# MidiMon_v3.net
KiCad netlist of a schematic drawn in EAGLE
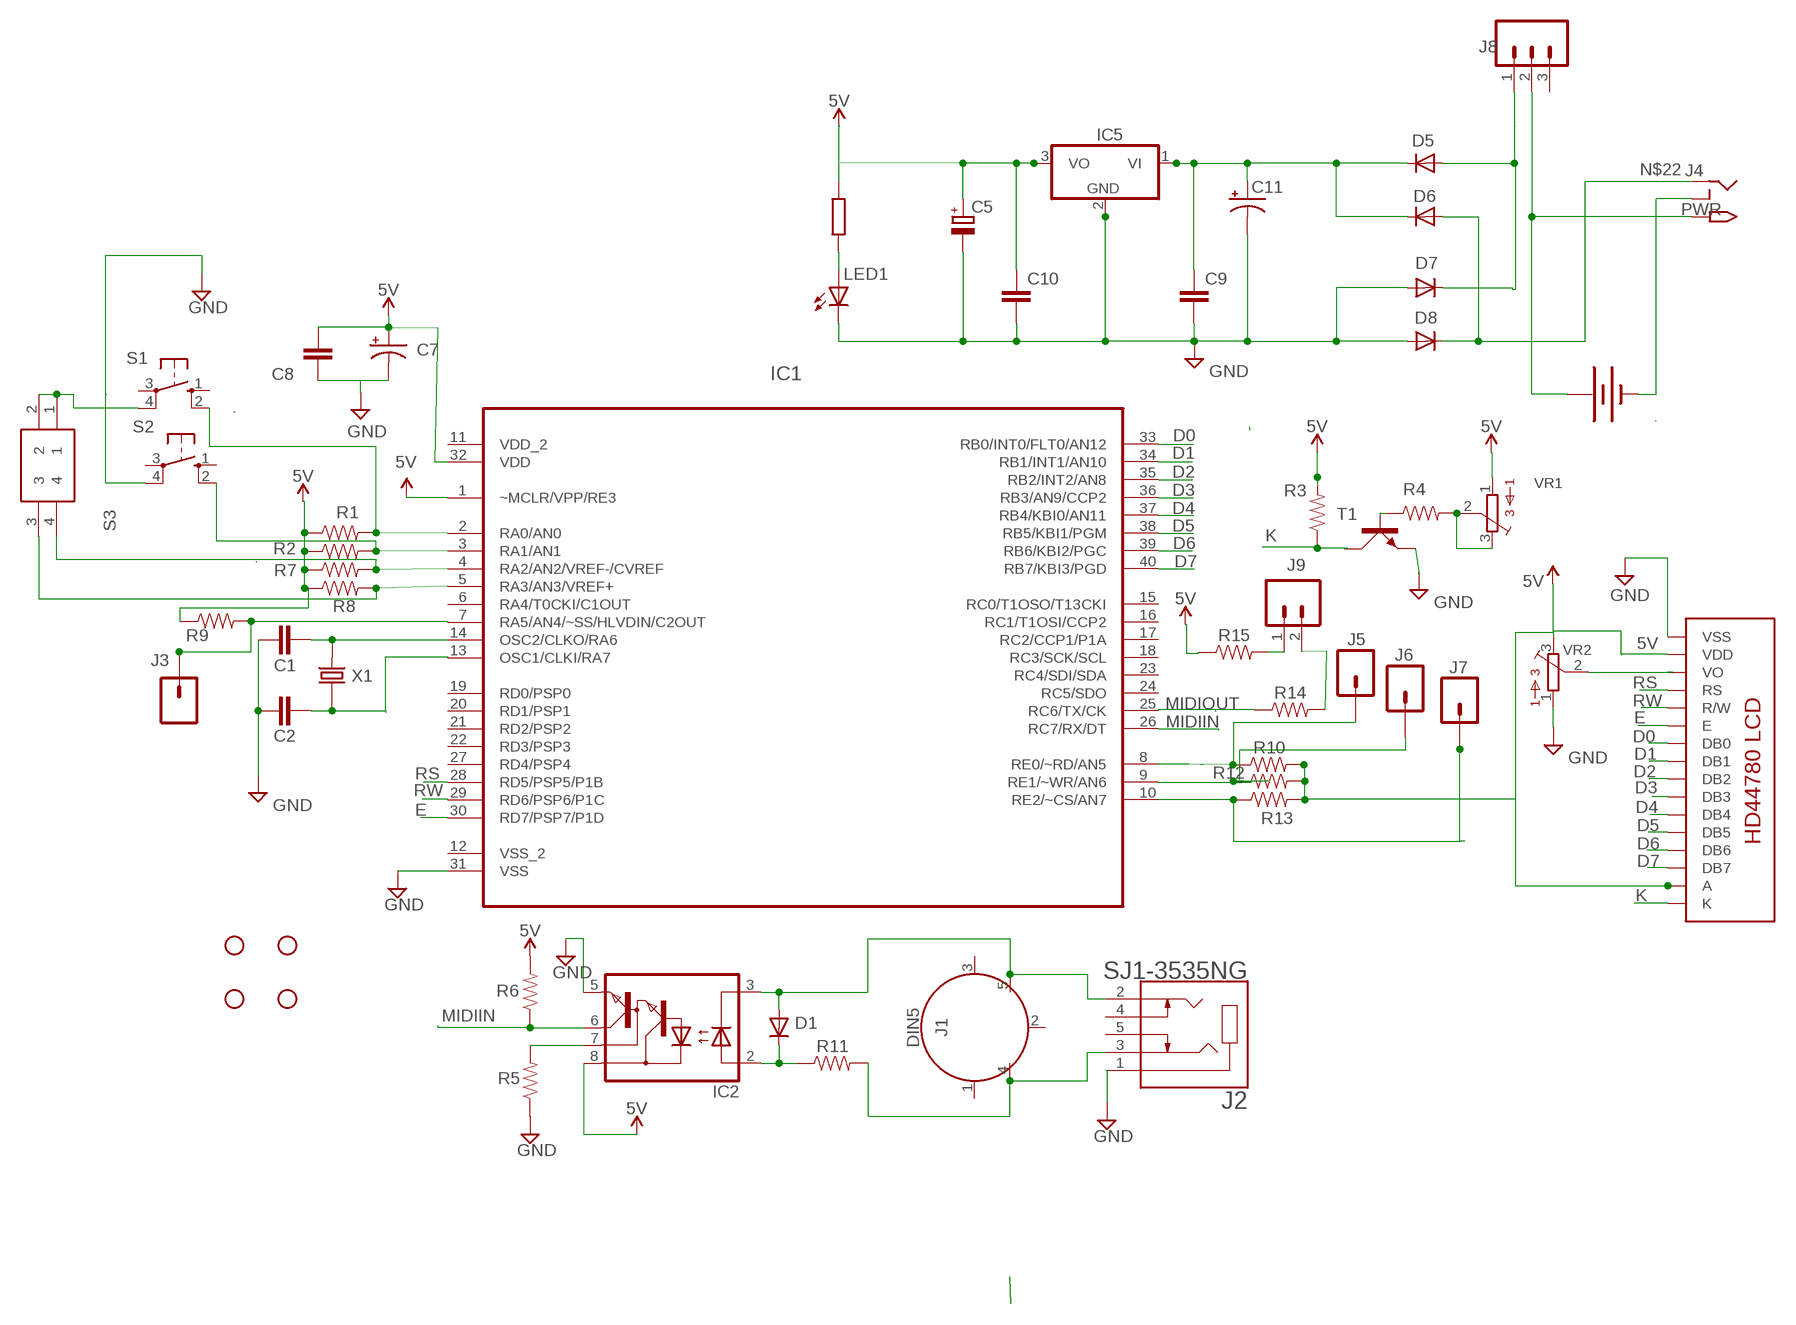
[diagram p0: schematic, sheet 1]

(export (version "E")
  (design (tool "Eeschema 10.0.6"))
  (components
    (comp (ref "BAT1")
      (value "BATTERY")
      (footprint "eagle-import:PP3_BATTERBOX")
      (libsource (lib "eagle-import") (part "BATTERY"))
    )
    (comp (ref "C1")
      (value "33pF")
      (footprint "eagle-import:CAP-PTH-2.54")
      (libsource (lib "eagle-import") (part "22PF-PTH-2.54MM-200V-5%"))
    )
    (comp (ref "C2")
      (value "33pF")
      (footprint "eagle-import:CAP-PTH-2.54")
      (libsource (lib "eagle-import") (part "22PF-PTH-2.54MM-200V-5%"))
    )
    (comp (ref "C5")
      (value "10uf")
      (footprint "eagle-import:E2,5-7")
      (libsource (lib "eagle-import") (part "CPOL-EUE2.5-7"))
    )
    (comp (ref "C7")
      (value "10uF")
      (footprint "eagle-import:CPOL-RADIAL-2.5MM-5MM")
      (libsource (lib "eagle-import") (part "10UF-POLAR-RADIAL-2.5MM-25V-20%"))
    )
    (comp (ref "C8")
      (value "0.1uF")
      (footprint "eagle-import:C025-024X044")
      (libsource (lib "eagle-import") (part "rcl_334_C-EU025-024X044"))
    )
    (comp (ref "C9")
      (value "330nf")
      (footprint "eagle-import:C025-024X044")
      (libsource (lib "eagle-import") (part "C-EU025-024X044"))
    )
    (comp (ref "C10")
      (value "100nf")
      (footprint "eagle-import:C025-024X044")
      (libsource (lib "eagle-import") (part "C-EU025-024X044"))
    )
    (comp (ref "C11")
      (value "2200uf")
      (footprint "eagle-import:E5-10,5")
      (libsource (lib "eagle-import") (part "CPOL-USE5-10.5"))
    )
    (comp (ref "D1")
      (value "DIODEDO-1N4148")
      (footprint "eagle-import:DO-1N4148")
      (libsource (lib "eagle-import") (part "DIODEDO-1N4148"))
    )
    (comp (ref "D5")
      (value "1N4004")
      (footprint "eagle-import:DO-VERT")
      (libsource (lib "eagle-import") (part "1N4004"))
    )
    (comp (ref "D6")
      (value "1N4004")
      (footprint "eagle-import:DO-VERT")
      (libsource (lib "eagle-import") (part "1N4004"))
    )
    (comp (ref "D7")
      (value "1N4004")
      (footprint "eagle-import:DO-VERT")
      (libsource (lib "eagle-import") (part "1N4004"))
    )
    (comp (ref "D8")
      (value "1N4004")
      (footprint "eagle-import:DO-VERT")
      (libsource (lib "eagle-import") (part "1N4004"))
    )
    (comp (ref "H1")
      (value "STAND-OFFTIGHT")
      (footprint "eagle-import:STAND-OFF-TIGHT")
      (libsource (lib "eagle-import") (part "STAND-OFFTIGHT"))
    )
    (comp (ref "H2")
      (value "STAND-OFFTIGHT")
      (footprint "eagle-import:STAND-OFF-TIGHT")
      (libsource (lib "eagle-import") (part "STAND-OFFTIGHT"))
    )
    (comp (ref "H3")
      (value "STAND-OFFTIGHT")
      (footprint "eagle-import:STAND-OFF-TIGHT")
      (libsource (lib "eagle-import") (part "STAND-OFFTIGHT"))
    )
    (comp (ref "H4")
      (value "STAND-OFFTIGHT")
      (footprint "eagle-import:STAND-OFF-TIGHT")
      (libsource (lib "eagle-import") (part "STAND-OFFTIGHT"))
    )
    (comp (ref "IC1")
      (value "PIC18F4520-I/P")
      (footprint "eagle-import:DIP254P1524X533-40")
      (fields (field (name "MF") "Microchip"))
      (libsource (lib "eagle-import") (part "PIC18F4520-I/P"))
    )
    (comp (ref "IC2")
      (value "6N138")
      (footprint "eagle-import:DIL08")
      (fields (field (name "MF") "VISHAY/TELEFUNKEN"))
      (libsource (lib "eagle-import") (part "6N138"))
    )
    (comp (ref "IC5")
      (value "7805TV")
      (footprint "eagle-import:TO220V")
      (libsource (lib "eagle-import") (part "78TV05"))
    )
    (comp (ref "J1")
      (value "DIN5")
      (footprint "eagle-import:DIN5-RA-PTH")
      (libsource (lib "eagle-import") (part "DIN5"))
    )
    (comp (ref "J2")
      (value "SJ1-3535NG")
      (footprint "eagle-import:CUI_SJ1-3535NG")
      (fields (field (name "MF") "CUI Inc."))
      (libsource (lib "eagle-import") (part "SJ1-3535NG"))
    )
    (comp (ref "J3")
      (value "CONN_01")
      (footprint "eagle-import:1X01")
      (libsource (lib "eagle-import") (part "CONN_01"))
    )
    (comp (ref "J4")
      (value "2.1MMJACKTHM")
      (footprint "eagle-import:PJ-102A")
      (libsource (lib "eagle-import") (part "2.1MMJACKTHM"))
    )
    (comp (ref "J5")
      (value "CONN_01")
      (footprint "eagle-import:1X01")
      (libsource (lib "eagle-import") (part "CONN_01"))
    )
    (comp (ref "J6")
      (value "CONN_01")
      (footprint "eagle-import:1X01")
      (libsource (lib "eagle-import") (part "CONN_01"))
    )
    (comp (ref "J7")
      (value "CONN_01")
      (footprint "eagle-import:1X01")
      (libsource (lib "eagle-import") (part "CONN_01"))
    )
    (comp (ref "J8")
      (value "CONN_03")
      (footprint "eagle-import:1X03")
      (libsource (lib "eagle-import") (part "CONN_03"))
    )
    (comp (ref "J9")
      (value "CONN_02")
      (footprint "eagle-import:1X02")
      (libsource (lib "eagle-import") (part "CONN_02"))
    )
    (comp (ref "LED1")
      (value "LED3MM")
      (footprint "eagle-import:LED3MM")
      (libsource (lib "eagle-import") (part "LED3MM"))
    )
    (comp (ref "R1")
      (value "10k")
      (footprint "eagle-import:AXIAL-0.3")
      (libsource (lib "eagle-import") (part "1KOHM-HORIZ-1/4W-5%"))
    )
    (comp (ref "R2")
      (value "10k")
      (footprint "eagle-import:AXIAL-0.3")
      (libsource (lib "eagle-import") (part "1KOHM-HORIZ-1/4W-5%"))
    )
    (comp (ref "R3")
      (value "10k")
      (footprint "eagle-import:AXIAL-0.3")
      (libsource (lib "eagle-import") (part "1KOHM-HORIZ-1/4W-5%"))
    )
    (comp (ref "R4")
      (value "1k")
      (footprint "eagle-import:AXIAL-0.3")
      (libsource (lib "eagle-import") (part "1KOHM-HORIZ-1/4W-5%"))
    )
    (comp (ref "R5")
      (value "5.6k")
      (footprint "eagle-import:AXIAL-0.3")
      (libsource (lib "eagle-import") (part "1KOHM-HORIZ-1/4W-5%"))
    )
    (comp (ref "R6")
      (value "1.2k")
      (footprint "eagle-import:AXIAL-0.3")
      (libsource (lib "eagle-import") (part "1KOHM-HORIZ-1/4W-5%"))
    )
    (comp (ref "R7")
      (value "10k")
      (footprint "eagle-import:AXIAL-0.3")
      (libsource (lib "eagle-import") (part "1KOHM-HORIZ-1/4W-5%"))
    )
    (comp (ref "R8")
      (value "10k")
      (footprint "eagle-import:AXIAL-0.3")
      (libsource (lib "eagle-import") (part "1KOHM-HORIZ-1/4W-5%"))
    )
    (comp (ref "R9")
      (value "10k")
      (footprint "eagle-import:AXIAL-0.3")
      (libsource (lib "eagle-import") (part "1KOHM-HORIZ-1/4W-5%"))
    )
    (comp (ref "R10")
      (value "10k")
      (footprint "eagle-import:AXIAL-0.3")
      (libsource (lib "eagle-import") (part "1KOHM-HORIZ-1/4W-5%"))
    )
    (comp (ref "R11")
      (value "220")
      (footprint "eagle-import:AXIAL-0.3")
      (libsource (lib "eagle-import") (part "1KOHM-HORIZ-1/4W-5%"))
    )
    (comp (ref "R12")
      (value "10k")
      (footprint "eagle-import:AXIAL-0.3")
      (libsource (lib "eagle-import") (part "1KOHM-HORIZ-1/4W-5%"))
    )
    (comp (ref "R13")
      (value "10k")
      (footprint "eagle-import:AXIAL-0.3")
      (libsource (lib "eagle-import") (part "1KOHM-HORIZ-1/4W-5%"))
    )
    (comp (ref "R14")
      (value "220")
      (footprint "eagle-import:AXIAL-0.3")
      (libsource (lib "eagle-import") (part "1KOHM-HORIZ-1/4W-5%"))
    )
    (comp (ref "R15")
      (value "220")
      (footprint "eagle-import:AXIAL-0.3")
      (libsource (lib "eagle-import") (part "1KOHM-HORIZ-1/4W-5%"))
    )
    (comp (ref "R20")
      (value "1k")
      (footprint "eagle-import:0207_7")
      (libsource (lib "eagle-import") (part "R-EU_0207/7"))
    )
    (comp (ref "S1")
      (value "40-XX")
      (footprint "eagle-import:B3F-40XX")
      (fields (field (name "MF") "OMRON COMPONENTS USA") (field (name "MPN") "B3F-4000"))
      (libsource (lib "eagle-import") (part "40-XX"))
    )
    (comp (ref "S2")
      (value "40-XX")
      (footprint "eagle-import:B3F-40XX")
      (fields (field (name "MF") "OMRON COMPONENTS USA") (field (name "MPN") "B3F-4000"))
      (libsource (lib "eagle-import") (part "40-XX"))
    )
    (comp (ref "S3")
      (value "195-2MST")
      (footprint "eagle-import:DIPS774W56P254L726H790Q4N")
      (fields (field (name "MOUSER_PART_NUMBER") "774-1952MST"))
      (libsource (lib "eagle-import") (part "195-2MST"))
    )
    (comp (ref "T1")
      (value "2N3904")
      (footprint "eagle-import:TO92D")
      (libsource (lib "eagle-import") (part "2N3904"))
    )
    (comp (ref "U$2")
      (value "LCD-HD4478020X4-3HOLES")
      (footprint "eagle-import:LCD-20X4-3HOLES")
      (libsource (lib "eagle-import") (part "LCD-HD4478020X4-3HOLES"))
    )
    (comp (ref "VR1")
      (value "BOURNS_3362P_TRIMMERP")
      (footprint "eagle-import:BOURNS_3362P_TRIMMER")
      (libsource (lib "eagle-import") (part "BOURNS_3362P_TRIMMERP"))
    )
    (comp (ref "VR2")
      (value "BOURNS_3362P_TRIMMERP")
      (footprint "eagle-import:BOURNS_3362P_TRIMMER")
      (libsource (lib "eagle-import") (part "BOURNS_3362P_TRIMMERP"))
    )
    (comp (ref "X1")
      (value "ECS-100-18-4X")
      (footprint "eagle-import:XTAL_ECS-100-18-4X")
      (fields (field (name "DIGI-KEY_PART_NUMBER") "X1080-ND") (field (name "MF") "ECS Inc."))
      (libsource (lib "eagle-import") (part "ECS-100-18-4X"))
    )
  )
  (nets
    (net (code "1") (name "/D0") (class "Default")
      (node (ref "IC1") (pin "33") (pinfunction "RB0/INT0/FLT0/AN12_33") (pintype "bidirectional"))
      (node (ref "U$2") (pin "P$7") (pinfunction "DB0_P$7") (pintype "bidirectional"))
    )
    (net (code "2") (name "/D1") (class "Default")
      (node (ref "IC1") (pin "34") (pinfunction "RB1/INT1/AN10_34") (pintype "bidirectional"))
      (node (ref "U$2") (pin "P$8") (pinfunction "DB1_P$8") (pintype "bidirectional"))
    )
    (net (code "3") (name "/D2") (class "Default")
      (node (ref "IC1") (pin "35") (pinfunction "RB2/INT2/AN8_35") (pintype "bidirectional"))
      (node (ref "U$2") (pin "P$9") (pinfunction "DB2_P$9") (pintype "bidirectional"))
    )
    (net (code "4") (name "/D3") (class "Default")
      (node (ref "IC1") (pin "36") (pinfunction "RB3/AN9/CCP2_36") (pintype "bidirectional"))
      (node (ref "U$2") (pin "P$10") (pinfunction "DB3_P$10") (pintype "bidirectional"))
    )
    (net (code "5") (name "/D4") (class "Default")
      (node (ref "IC1") (pin "37") (pinfunction "RB4/KBI0/AN11_37") (pintype "bidirectional"))
      (node (ref "U$2") (pin "P$11") (pinfunction "DB4_P$11") (pintype "bidirectional"))
    )
    (net (code "6") (name "/D5") (class "Default")
      (node (ref "IC1") (pin "38") (pinfunction "RB5/KBI1/PGM_38") (pintype "bidirectional"))
      (node (ref "U$2") (pin "P$12") (pinfunction "DB5_P$12") (pintype "bidirectional"))
    )
    (net (code "7") (name "/D6") (class "Default")
      (node (ref "IC1") (pin "39") (pinfunction "RB6/KBI2/PGC_39") (pintype "bidirectional"))
      (node (ref "U$2") (pin "P$13") (pinfunction "DB6_P$13") (pintype "bidirectional"))
    )
    (net (code "8") (name "/D7") (class "Default")
      (node (ref "IC1") (pin "40") (pinfunction "RB7/KBI3/PGD_40") (pintype "bidirectional"))
      (node (ref "U$2") (pin "P$14") (pinfunction "DB7_P$14") (pintype "bidirectional"))
    )
    (net (code "9") (name "/E") (class "Default")
      (node (ref "IC1") (pin "30") (pinfunction "RD7/PSP7/P1D_30") (pintype "bidirectional"))
      (node (ref "U$2") (pin "P$6") (pinfunction "E_P$6") (pintype "input"))
    )
    (net (code "10") (name "/K") (class "Default")
      (node (ref "R3") (pin "P$1") (pinfunction "1_P$1") (pintype "passive"))
      (node (ref "T1") (pin "C") (pinfunction "C_C") (pintype "passive"))
      (node (ref "U$2") (pin "P$16") (pinfunction "K_P$16") (pintype "power_in"))
    )
    (net (code "11") (name "/MIDIIN") (class "Default")
      (node (ref "IC1") (pin "26") (pinfunction "RC7/RX/DT_26") (pintype "bidirectional"))
      (node (ref "IC2") (pin "6") (pinfunction "VO_6") (pintype "passive"))
      (node (ref "R6") (pin "P$1") (pinfunction "1_P$1") (pintype "passive"))
    )
    (net (code "13") (name "/N$22") (class "Default")
      (node (ref "D6") (pin "A") (pinfunction "A_A") (pintype "passive"))
      (node (ref "D8") (pin "C") (pinfunction "C_C") (pintype "passive"))
      (node (ref "J4") (pin "RING") (pinfunction "RING_RING") (pintype "bidirectional"))
    )
    (net (code "14") (name "/PWR") (class "Default")
      (node (ref "BAT1") (pin "9V") (pinfunction "+_9V") (pintype "power_in"))
      (node (ref "J4") (pin "TIP") (pinfunction "TIP_TIP") (pintype "bidirectional"))
      (node (ref "J8") (pin "2") (pinfunction "2_2") (pintype "passive"))
    )
    (net (code "15") (name "/RS") (class "Default")
      (node (ref "IC1") (pin "28") (pinfunction "RD5/PSP5/P1B_28") (pintype "bidirectional"))
      (node (ref "U$2") (pin "P$4") (pinfunction "RS_P$4") (pintype "input"))
    )
    (net (code "16") (name "/RW") (class "Default")
      (node (ref "IC1") (pin "29") (pinfunction "RD6/PSP6/P1C_29") (pintype "bidirectional"))
      (node (ref "U$2") (pin "P$5") (pinfunction "R/W_P$5") (pintype "input"))
    )
    (net (code "17") (name "/VDD_2") (class "Default")
      (node (ref "IC1") (pin "11") (pinfunction "VDD_2_11") (pintype "power_in"))
    )
    (net (code "18") (name "/VSS_2") (class "Default")
      (node (ref "IC1") (pin "12") (pinfunction "VSS_2_12") (pintype "power_in"))
    )
    (net (code "19") (name "5V") (class "Default")
      (node (ref "C10") (pin "1") (pinfunction "1_1") (pintype "passive"))
      (node (ref "C5") (pin "+") (pinfunction "+_+") (pintype "passive"))
      (node (ref "C7") (pin "1") (pinfunction "+_1") (pintype "passive"))
      (node (ref "C8") (pin "2") (pinfunction "2_2") (pintype "passive"))
      (node (ref "IC1") (pin "1") (pinfunction "~{MCLR/VPP/RE3}_1") (pintype "input"))
      (node (ref "IC1") (pin "32") (pinfunction "VDD_32") (pintype "power_in"))
      (node (ref "IC2") (pin "8") (pinfunction "VCC_8") (pintype "passive"))
      (node (ref "IC5") (pin "3") (pinfunction "VO_3") (pintype "passive"))
      (node (ref "R1") (pin "P$1") (pinfunction "1_P$1") (pintype "passive"))
      (node (ref "R10") (pin "P$2") (pinfunction "2_P$2") (pintype "passive"))
      (node (ref "R12") (pin "P$2") (pinfunction "2_P$2") (pintype "passive"))
      (node (ref "R13") (pin "P$2") (pinfunction "2_P$2") (pintype "passive"))
      (node (ref "R15") (pin "P$1") (pinfunction "1_P$1") (pintype "passive"))
      (node (ref "R2") (pin "P$1") (pinfunction "1_P$1") (pintype "passive"))
      (node (ref "R20") (pin "1") (pinfunction "1_1") (pintype "passive"))
      (node (ref "R3") (pin "P$2") (pinfunction "2_P$2") (pintype "passive"))
      (node (ref "R6") (pin "P$2") (pinfunction "2_P$2") (pintype "passive"))
      (node (ref "R7") (pin "P$1") (pinfunction "1_P$1") (pintype "passive"))
      (node (ref "R8") (pin "P$1") (pinfunction "1_P$1") (pintype "passive"))
      (node (ref "R9") (pin "P$1") (pinfunction "1_P$1") (pintype "passive"))
      (node (ref "U$2") (pin "P$15") (pinfunction "A_P$15") (pintype "power_in"))
      (node (ref "U$2") (pin "P$2") (pinfunction "VDD_P$2") (pintype "power_in"))
      (node (ref "VR1") (pin "1") (pinfunction "1_1") (pintype "passive"))
      (node (ref "VR2") (pin "3") (pinfunction "3_3") (pintype "passive"))
    )
    (net (code "20") (name "GND") (class "Default")
      (node (ref "C1") (pin "1") (pinfunction "1_1") (pintype "passive"))
      (node (ref "C10") (pin "2") (pinfunction "2_2") (pintype "passive"))
      (node (ref "C11") (pin "-") (pinfunction "-_-") (pintype "passive"))
      (node (ref "C2") (pin "1") (pinfunction "1_1") (pintype "passive"))
      (node (ref "C5") (pin "-") (pinfunction "-_-") (pintype "passive"))
      (node (ref "C7") (pin "2") (pinfunction "-_2") (pintype "passive"))
      (node (ref "C8") (pin "1") (pinfunction "1_1") (pintype "passive"))
      (node (ref "C9") (pin "2") (pinfunction "2_2") (pintype "passive"))
      (node (ref "D7") (pin "A") (pinfunction "A_A") (pintype "passive"))
      (node (ref "D8") (pin "A") (pinfunction "A_A") (pintype "passive"))
      (node (ref "IC1") (pin "31") (pinfunction "VSS_31") (pintype "power_in"))
      (node (ref "IC2") (pin "5") (pinfunction "GND_5") (pintype "passive"))
      (node (ref "IC5") (pin "2") (pinfunction "GND_2") (pintype "passive"))
      (node (ref "J2") (pin "1") (pinfunction "1_1") (pintype "passive"))
      (node (ref "LED1") (pin "K") (pinfunction "C_K") (pintype "passive"))
      (node (ref "R5") (pin "P$1") (pinfunction "1_P$1") (pintype "passive"))
      (node (ref "S1") (pin "4") (pinfunction "P1_4") (pintype "passive"))
      (node (ref "S2") (pin "4") (pinfunction "P1_4") (pintype "passive"))
      (node (ref "S3") (pin "1") (pinfunction "1_1") (pintype "bidirectional"))
      (node (ref "S3") (pin "2") (pinfunction "2_2") (pintype "bidirectional"))
      (node (ref "T1") (pin "E") (pinfunction "E_E") (pintype "passive"))
      (node (ref "U$2") (pin "P$1") (pinfunction "VSS_P$1") (pintype "power_in"))
      (node (ref "VR2") (pin "1") (pinfunction "1_1") (pintype "passive"))
    )
    (net (code "21") (name "Net-(BAT1--)") (class "Default")
      (node (ref "BAT1") (pin "0V") (pinfunction "-_0V") (pintype "power_in"))
      (node (ref "J4") (pin "RING_SW") (pinfunction "RING_SW_RING_SW") (pintype "bidirectional"))
    )
    (net (code "22") (name "Net-(D5-PadA)") (class "Default")
      (node (ref "D5") (pin "A") (pinfunction "A_A") (pintype "passive"))
      (node (ref "D7") (pin "C") (pinfunction "C_C") (pintype "passive"))
      (node (ref "J8") (pin "1") (pinfunction "1_1") (pintype "passive"))
    )
    (net (code "23") (name "Net-(IC1-OSC1{slash}CLKI{slash}RA7)") (class "Default")
      (node (ref "C2") (pin "2") (pinfunction "2_2") (pintype "passive"))
      (node (ref "IC1") (pin "13") (pinfunction "OSC1/CLKI/RA7_13") (pintype "bidirectional"))
      (node (ref "X1") (pin "1") (pinfunction "1_1") (pintype "passive"))
    )
    (net (code "24") (name "Net-(IC1-OSC2{slash}CLKO{slash}RA6)") (class "Default")
      (node (ref "C1") (pin "2") (pinfunction "2_2") (pintype "passive"))
      (node (ref "IC1") (pin "14") (pinfunction "OSC2/CLKO/RA6_14") (pintype "bidirectional"))
      (node (ref "X1") (pin "2") (pinfunction "2_2") (pintype "passive"))
    )
    (net (code "25") (name "Net-(IC1-RA0{slash}AN0)") (class "Default")
      (node (ref "IC1") (pin "2") (pinfunction "RA0/AN0_2") (pintype "bidirectional"))
      (node (ref "R1") (pin "P$2") (pinfunction "2_P$2") (pintype "passive"))
      (node (ref "S1") (pin "2") (pinfunction "S1_2") (pintype "passive"))
    )
    (net (code "26") (name "Net-(IC1-RA1{slash}AN1)") (class "Default")
      (node (ref "IC1") (pin "3") (pinfunction "RA1/AN1_3") (pintype "bidirectional"))
      (node (ref "R2") (pin "P$2") (pinfunction "2_P$2") (pintype "passive"))
      (node (ref "S2") (pin "2") (pinfunction "S1_2") (pintype "passive"))
    )
    (net (code "27") (name "Net-(IC1-RA2{slash}AN2{slash}VREF-{slash}CVREF)") (class "Default")
      (node (ref "IC1") (pin "4") (pinfunction "RA2/AN2/VREF-/CVREF_4") (pintype "bidirectional"))
      (node (ref "R7") (pin "P$2") (pinfunction "2_P$2") (pintype "passive"))
      (node (ref "S3") (pin "4") (pinfunction "4_4") (pintype "bidirectional"))
    )
    (net (code "28") (name "Net-(IC1-RA3{slash}AN3{slash}VREF+)") (class "Default")
      (node (ref "IC1") (pin "5") (pinfunction "RA3/AN3/VREF+_5") (pintype "bidirectional"))
      (node (ref "R8") (pin "P$2") (pinfunction "2_P$2") (pintype "passive"))
      (node (ref "S3") (pin "3") (pinfunction "3_3") (pintype "bidirectional"))
    )
    (net (code "29") (name "Net-(IC1-RA5{slash}AN4{slash}~{SS{slash}HLVDIN{slash}C2OUT})") (class "Default")
      (node (ref "IC1") (pin "7") (pinfunction "RA5/AN4/~{SS/HLVDIN/C2OUT}_7") (pintype "bidirectional"))
      (node (ref "J3") (pin "1") (pinfunction "1_1") (pintype "passive"))
      (node (ref "R9") (pin "P$2") (pinfunction "2_P$2") (pintype "passive"))
    )
    (net (code "30") (name "Net-(IC1-RC6{slash}TX{slash}CK)") (class "Default")
      (node (ref "IC1") (pin "25") (pinfunction "RC6/TX/CK_25") (pintype "bidirectional"))
      (node (ref "R14") (pin "P$1") (pinfunction "1_P$1") (pintype "passive"))
    )
    (net (code "31") (name "Net-(IC1-RE0{slash}~{RD{slash}AN5})") (class "Default")
      (node (ref "IC1") (pin "8") (pinfunction "RE0/~{RD/AN5}_8") (pintype "bidirectional"))
      (node (ref "J5") (pin "1") (pinfunction "1_1") (pintype "passive"))
      (node (ref "R10") (pin "P$1") (pinfunction "1_P$1") (pintype "passive"))
    )
    (net (code "32") (name "Net-(IC1-RE1{slash}~{WR{slash}AN6})") (class "Default")
      (node (ref "IC1") (pin "9") (pinfunction "RE1/~{WR/AN6}_9") (pintype "bidirectional"))
      (node (ref "J6") (pin "1") (pinfunction "1_1") (pintype "passive"))
      (node (ref "R12") (pin "P$1") (pinfunction "1_P$1") (pintype "passive"))
    )
    (net (code "33") (name "Net-(IC1-RE2{slash}~{CS{slash}AN7})") (class "Default")
      (node (ref "IC1") (pin "10") (pinfunction "RE2/~{CS/AN7}_10") (pintype "bidirectional"))
      (node (ref "J7") (pin "1") (pinfunction "1_1") (pintype "passive"))
      (node (ref "R13") (pin "P$1") (pinfunction "1_P$1") (pintype "passive"))
    )
    (net (code "34") (name "Net-(IC2-A)") (class "Default")
      (node (ref "D1") (pin "C") (pinfunction "C_C") (pintype "passive"))
      (node (ref "IC2") (pin "2") (pinfunction "A_2") (pintype "passive"))
      (node (ref "R11") (pin "P$1") (pinfunction "1_P$1") (pintype "passive"))
    )
    (net (code "35") (name "Net-(IC2-C)") (class "Default")
      (node (ref "D1") (pin "A") (pinfunction "A_A") (pintype "passive"))
      (node (ref "IC2") (pin "3") (pinfunction "C_3") (pintype "passive"))
      (node (ref "J1") (pin "5") (pinfunction "5_5") (pintype "bidirectional"))
      (node (ref "J2") (pin "2") (pinfunction "2_2") (pintype "passive"))
    )
    (net (code "36") (name "Net-(IC2-VB)") (class "Default")
      (node (ref "IC2") (pin "7") (pinfunction "VB_7") (pintype "passive"))
      (node (ref "R5") (pin "P$2") (pinfunction "2_P$2") (pintype "passive"))
    )
    (net (code "37") (name "Net-(IC5-VI)") (class "Default")
      (node (ref "C11") (pin "+") (pinfunction "+_+") (pintype "passive"))
      (node (ref "C9") (pin "1") (pinfunction "1_1") (pintype "passive"))
      (node (ref "D5") (pin "C") (pinfunction "C_C") (pintype "passive"))
      (node (ref "D6") (pin "C") (pinfunction "C_C") (pintype "passive"))
      (node (ref "IC5") (pin "1") (pinfunction "VI_1") (pintype "input"))
    )
    (net (code "38") (name "Net-(LED1-PadA)") (class "Default")
      (node (ref "LED1") (pin "A") (pinfunction "A_A") (pintype "passive"))
      (node (ref "R20") (pin "2") (pinfunction "2_2") (pintype "passive"))
    )
    (net (code "39") (name "Net-(R4-1)") (class "Default")
      (node (ref "R4") (pin "P$1") (pinfunction "1_P$1") (pintype "passive"))
      (node (ref "T1") (pin "B") (pinfunction "B_B") (pintype "passive"))
    )
    (net (code "40") (name "Net-(R4-2)") (class "Default")
      (node (ref "R4") (pin "P$2") (pinfunction "2_P$2") (pintype "passive"))
      (node (ref "VR1") (pin "2") (pinfunction "2_2") (pintype "passive"))
      (node (ref "VR1") (pin "3") (pinfunction "3_3") (pintype "passive"))
    )
    (net (code "41") (name "Net-(R11-2)") (class "Default")
      (node (ref "J1") (pin "4") (pinfunction "4_4") (pintype "bidirectional"))
      (node (ref "J2") (pin "3") (pinfunction "3_3") (pintype "passive"))
      (node (ref "R11") (pin "P$2") (pinfunction "2_P$2") (pintype "passive"))
    )
    (net (code "42") (name "Net-(R14-2)") (class "Default")
      (node (ref "J9") (pin "2") (pinfunction "2_2") (pintype "passive"))
      (node (ref "R14") (pin "P$2") (pinfunction "2_P$2") (pintype "passive"))
    )
    (net (code "43") (name "Net-(R15-2)") (class "Default")
      (node (ref "J9") (pin "1") (pinfunction "1_1") (pintype "passive"))
      (node (ref "R15") (pin "P$2") (pinfunction "2_P$2") (pintype "passive"))
    )
    (net (code "44") (name "Net-(U$2-VO)") (class "Default")
      (node (ref "U$2") (pin "P$3") (pinfunction "VO_P$3") (pintype "bidirectional"))
      (node (ref "VR2") (pin "2") (pinfunction "2_2") (pintype "passive"))
    )
    (net (code "45") (name "unconnected-(IC1-RA4{slash}T0CKI{slash}C1OUT-Pad6)") (class "Default")
      (node (ref "IC1") (pin "6") (pinfunction "RA4/T0CKI/C1OUT_6") (pintype "bidirectional"))
    )
    (net (code "46") (name "unconnected-(IC1-RC0{slash}T1OSO{slash}T13CKI-Pad15)") (class "Default")
      (node (ref "IC1") (pin "15") (pinfunction "RC0/T1OSO/T13CKI_15") (pintype "bidirectional"))
    )
    (net (code "47") (name "unconnected-(IC1-RC1{slash}T1OSI{slash}CCP2-Pad16)") (class "Default")
      (node (ref "IC1") (pin "16") (pinfunction "RC1/T1OSI/CCP2_16") (pintype "bidirectional"))
    )
    (net (code "48") (name "unconnected-(IC1-RC2{slash}CCP1{slash}P1A-Pad17)") (class "Default")
      (node (ref "IC1") (pin "17") (pinfunction "RC2/CCP1/P1A_17") (pintype "bidirectional"))
    )
    (net (code "49") (name "unconnected-(IC1-RC3{slash}SCK{slash}SCL-Pad18)") (class "Default")
      (node (ref "IC1") (pin "18") (pinfunction "RC3/SCK/SCL_18") (pintype "bidirectional"))
    )
    (net (code "50") (name "unconnected-(IC1-RC4{slash}SDI{slash}SDA-Pad23)") (class "Default")
      (node (ref "IC1") (pin "23") (pinfunction "RC4/SDI/SDA_23") (pintype "bidirectional"))
    )
    (net (code "51") (name "unconnected-(IC1-RC5{slash}SDO-Pad24)") (class "Default")
      (node (ref "IC1") (pin "24") (pinfunction "RC5/SDO_24") (pintype "bidirectional"))
    )
    (net (code "52") (name "unconnected-(IC1-RD0{slash}PSP0-Pad19)") (class "Default")
      (node (ref "IC1") (pin "19") (pinfunction "RD0/PSP0_19") (pintype "bidirectional"))
    )
    (net (code "53") (name "unconnected-(IC1-RD1{slash}PSP1-Pad20)") (class "Default")
      (node (ref "IC1") (pin "20") (pinfunction "RD1/PSP1_20") (pintype "bidirectional"))
    )
    (net (code "54") (name "unconnected-(IC1-RD2{slash}PSP2-Pad21)") (class "Default")
      (node (ref "IC1") (pin "21") (pinfunction "RD2/PSP2_21") (pintype "bidirectional"))
    )
    (net (code "55") (name "unconnected-(IC1-RD3{slash}PSP3-Pad22)") (class "Default")
      (node (ref "IC1") (pin "22") (pinfunction "RD3/PSP3_22") (pintype "bidirectional"))
    )
    (net (code "56") (name "unconnected-(IC1-RD4{slash}PSP4-Pad27)") (class "Default")
      (node (ref "IC1") (pin "27") (pinfunction "RD4/PSP4_27") (pintype "bidirectional"))
    )
    (net (code "57") (name "unconnected-(J1-Pad1)") (class "Default")
      (node (ref "J1") (pin "1") (pinfunction "1_1") (pintype "bidirectional"))
    )
    (net (code "58") (name "unconnected-(J1-Pad2)") (class "Default")
      (node (ref "J1") (pin "2") (pinfunction "2_2") (pintype "bidirectional"))
    )
    (net (code "59") (name "unconnected-(J1-Pad3)") (class "Default")
      (node (ref "J1") (pin "3") (pinfunction "3_3") (pintype "bidirectional"))
    )
    (net (code "60") (name "unconnected-(J2-Pad4)") (class "Default")
      (node (ref "J2") (pin "4") (pinfunction "4_4") (pintype "passive"))
    )
    (net (code "61") (name "unconnected-(J2-Pad5)") (class "Default")
      (node (ref "J2") (pin "5") (pinfunction "5_5") (pintype "passive"))
    )
    (net (code "62") (name "unconnected-(J8-Pad3)") (class "Default")
      (node (ref "J8") (pin "3") (pinfunction "3_3") (pintype "passive"))
    )
    (net (code "63") (name "unconnected-(S1-P-Pad3)") (class "Default")
      (node (ref "S1") (pin "3") (pinfunction "P_3") (pintype "passive"))
    )
    (net (code "64") (name "unconnected-(S1-S-Pad1)") (class "Default")
      (node (ref "S1") (pin "1") (pinfunction "S_1") (pintype "passive"))
    )
    (net (code "65") (name "unconnected-(S2-P-Pad3)") (class "Default")
      (node (ref "S2") (pin "3") (pinfunction "P_3") (pintype "passive"))
    )
    (net (code "66") (name "unconnected-(S2-S-Pad1)") (class "Default")
      (node (ref "S2") (pin "1") (pinfunction "S_1") (pintype "passive"))
    )
  )
)
